# leptetomotor.net
KiCad netlist of a schematic drawn in EAGLE
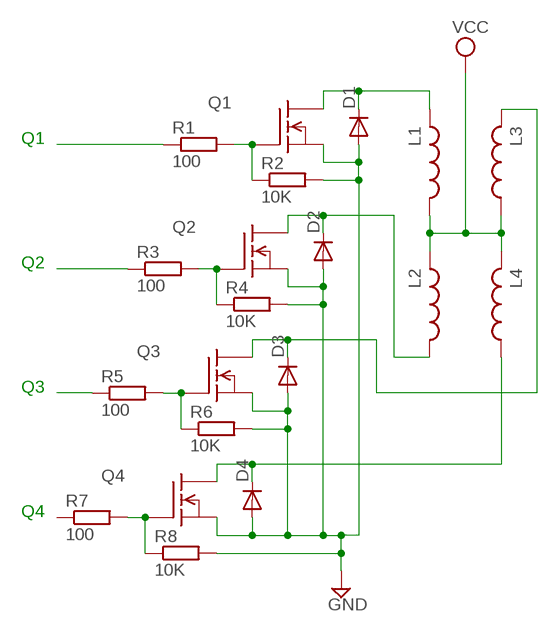
[diagram p0: schematic, sheet 1]

(export (version "E")
  (design (tool "Eeschema 10.0.6"))
  (components
    (comp (ref "D1")
      (value "1N4004")
      (footprint "eagle-import:DO41-10")
      (libsource (lib "eagle-import") (part "1N4004"))
    )
    (comp (ref "D2")
      (value "1N4004")
      (footprint "eagle-import:DO41-10")
      (libsource (lib "eagle-import") (part "1N4004"))
    )
    (comp (ref "D3")
      (value "1N4004")
      (footprint "eagle-import:DO41-10")
      (libsource (lib "eagle-import") (part "1N4004"))
    )
    (comp (ref "D4")
      (value "1N4004")
      (footprint "eagle-import:DO41-10")
      (libsource (lib "eagle-import") (part "1N4004"))
    )
    (comp (ref "L1")
      (value "L-US0204/5")
      (footprint "eagle-import:0204_5")
      (libsource (lib "eagle-import") (part "L-US0204/5"))
    )
    (comp (ref "L2")
      (value "L-US0204/5")
      (footprint "eagle-import:0204_5")
      (libsource (lib "eagle-import") (part "L-US0204/5"))
    )
    (comp (ref "L3")
      (value "L-US0204/5")
      (footprint "eagle-import:0204_5")
      (libsource (lib "eagle-import") (part "L-US0204/5"))
    )
    (comp (ref "L4")
      (value "L-US0204/5")
      (footprint "eagle-import:0204_5")
      (libsource (lib "eagle-import") (part "L-US0204/5"))
    )
    (comp (ref "Q1")
      (value "BUZ10")
      (footprint "eagle-import:TO220")
      (libsource (lib "eagle-import") (part "BUZ10"))
    )
    (comp (ref "Q2")
      (value "BUZ10")
      (footprint "eagle-import:TO220")
      (libsource (lib "eagle-import") (part "BUZ10"))
    )
    (comp (ref "Q3")
      (value "BUZ10")
      (footprint "eagle-import:TO220")
      (libsource (lib "eagle-import") (part "BUZ10"))
    )
    (comp (ref "Q4")
      (value "BUZ10")
      (footprint "eagle-import:TO220")
      (libsource (lib "eagle-import") (part "BUZ10"))
    )
    (comp (ref "R1")
      (value "100")
      (footprint "eagle-import:VMTB60")
      (libsource (lib "eagle-import") (part "R-EU_VMTB60"))
    )
    (comp (ref "R2")
      (value "10K")
      (footprint "eagle-import:VMTB60")
      (libsource (lib "eagle-import") (part "R-EU_VMTB60"))
    )
    (comp (ref "R3")
      (value "100")
      (footprint "eagle-import:VMTB60")
      (libsource (lib "eagle-import") (part "R-EU_VMTB60"))
    )
    (comp (ref "R4")
      (value "10K")
      (footprint "eagle-import:VMTB60")
      (libsource (lib "eagle-import") (part "R-EU_VMTB60"))
    )
    (comp (ref "R5")
      (value "100")
      (footprint "eagle-import:VMTB60")
      (libsource (lib "eagle-import") (part "R-EU_VMTB60"))
    )
    (comp (ref "R6")
      (value "10K")
      (footprint "eagle-import:VMTB60")
      (libsource (lib "eagle-import") (part "R-EU_VMTB60"))
    )
    (comp (ref "R7")
      (value "100")
      (footprint "eagle-import:VMTB60")
      (libsource (lib "eagle-import") (part "R-EU_VMTB60"))
    )
    (comp (ref "R8")
      (value "10K")
      (footprint "eagle-import:VMTB60")
      (libsource (lib "eagle-import") (part "R-EU_VMTB60"))
    )
  )
  (nets
    (net (code "1") (name "GND") (class "Default")
      (node (ref "D1") (pin "A") (pinfunction "A_A") (pintype "passive"))
      (node (ref "D2") (pin "A") (pinfunction "A_A") (pintype "passive"))
      (node (ref "D3") (pin "A") (pinfunction "A_A") (pintype "passive"))
      (node (ref "D4") (pin "A") (pinfunction "A_A") (pintype "passive"))
      (node (ref "Q1") (pin "3") (pinfunction "S_3") (pintype "passive"))
      (node (ref "Q2") (pin "3") (pinfunction "S_3") (pintype "passive"))
      (node (ref "Q3") (pin "3") (pinfunction "S_3") (pintype "passive"))
      (node (ref "Q4") (pin "3") (pinfunction "S_3") (pintype "passive"))
      (node (ref "R2") (pin "2") (pinfunction "2_2") (pintype "passive"))
      (node (ref "R4") (pin "2") (pinfunction "2_2") (pintype "passive"))
      (node (ref "R6") (pin "2") (pinfunction "2_2") (pintype "passive"))
      (node (ref "R8") (pin "2") (pinfunction "2_2") (pintype "passive"))
    )
    (net (code "2") (name "Net-(Q1-D)") (class "Default")
      (node (ref "D1") (pin "C") (pinfunction "C_C") (pintype "passive"))
      (node (ref "L1") (pin "2") (pinfunction "2_2") (pintype "passive"))
      (node (ref "Q1") (pin "2") (pinfunction "D_2") (pintype "passive"))
    )
    (net (code "3") (name "Net-(Q1-G)") (class "Default")
      (node (ref "Q1") (pin "1") (pinfunction "G_1") (pintype "passive"))
      (node (ref "R1") (pin "2") (pinfunction "2_2") (pintype "passive"))
      (node (ref "R2") (pin "1") (pinfunction "1_1") (pintype "passive"))
    )
    (net (code "4") (name "Net-(Q2-D)") (class "Default")
      (node (ref "D2") (pin "C") (pinfunction "C_C") (pintype "passive"))
      (node (ref "L2") (pin "1") (pinfunction "1_1") (pintype "passive"))
      (node (ref "Q2") (pin "2") (pinfunction "D_2") (pintype "passive"))
    )
    (net (code "5") (name "Net-(Q2-G)") (class "Default")
      (node (ref "Q2") (pin "1") (pinfunction "G_1") (pintype "passive"))
      (node (ref "R3") (pin "2") (pinfunction "2_2") (pintype "passive"))
      (node (ref "R4") (pin "1") (pinfunction "1_1") (pintype "passive"))
    )
    (net (code "6") (name "Net-(Q3-D)") (class "Default")
      (node (ref "D3") (pin "C") (pinfunction "C_C") (pintype "passive"))
      (node (ref "L3") (pin "2") (pinfunction "2_2") (pintype "passive"))
      (node (ref "Q3") (pin "2") (pinfunction "D_2") (pintype "passive"))
    )
    (net (code "7") (name "Net-(Q3-G)") (class "Default")
      (node (ref "Q3") (pin "1") (pinfunction "G_1") (pintype "passive"))
      (node (ref "R5") (pin "2") (pinfunction "2_2") (pintype "passive"))
      (node (ref "R6") (pin "1") (pinfunction "1_1") (pintype "passive"))
    )
    (net (code "8") (name "Net-(Q4-D)") (class "Default")
      (node (ref "D4") (pin "C") (pinfunction "C_C") (pintype "passive"))
      (node (ref "L4") (pin "1") (pinfunction "1_1") (pintype "passive"))
      (node (ref "Q4") (pin "2") (pinfunction "D_2") (pintype "passive"))
    )
    (net (code "9") (name "Net-(Q4-G)") (class "Default")
      (node (ref "Q4") (pin "1") (pinfunction "G_1") (pintype "passive"))
      (node (ref "R7") (pin "2") (pinfunction "2_2") (pintype "passive"))
      (node (ref "R8") (pin "1") (pinfunction "1_1") (pintype "passive"))
    )
    (net (code "10") (name "VCC") (class "Default")
      (node (ref "L1") (pin "1") (pinfunction "1_1") (pintype "passive"))
      (node (ref "L2") (pin "2") (pinfunction "2_2") (pintype "passive"))
      (node (ref "L3") (pin "1") (pinfunction "1_1") (pintype "passive"))
      (node (ref "L4") (pin "2") (pinfunction "2_2") (pintype "passive"))
    )
    (net (code "11") (name "unconnected-(R1-Pad1)") (class "Default")
      (node (ref "R1") (pin "1") (pinfunction "1_1") (pintype "passive"))
    )
    (net (code "12") (name "unconnected-(R3-Pad1)") (class "Default")
      (node (ref "R3") (pin "1") (pinfunction "1_1") (pintype "passive"))
    )
    (net (code "13") (name "unconnected-(R5-Pad1)") (class "Default")
      (node (ref "R5") (pin "1") (pinfunction "1_1") (pintype "passive"))
    )
    (net (code "14") (name "unconnected-(R7-Pad1)") (class "Default")
      (node (ref "R7") (pin "1") (pinfunction "1_1") (pintype "passive"))
    )
  )
)
